# gravicapa.net
KiCad netlist of a schematic drawn in EAGLE
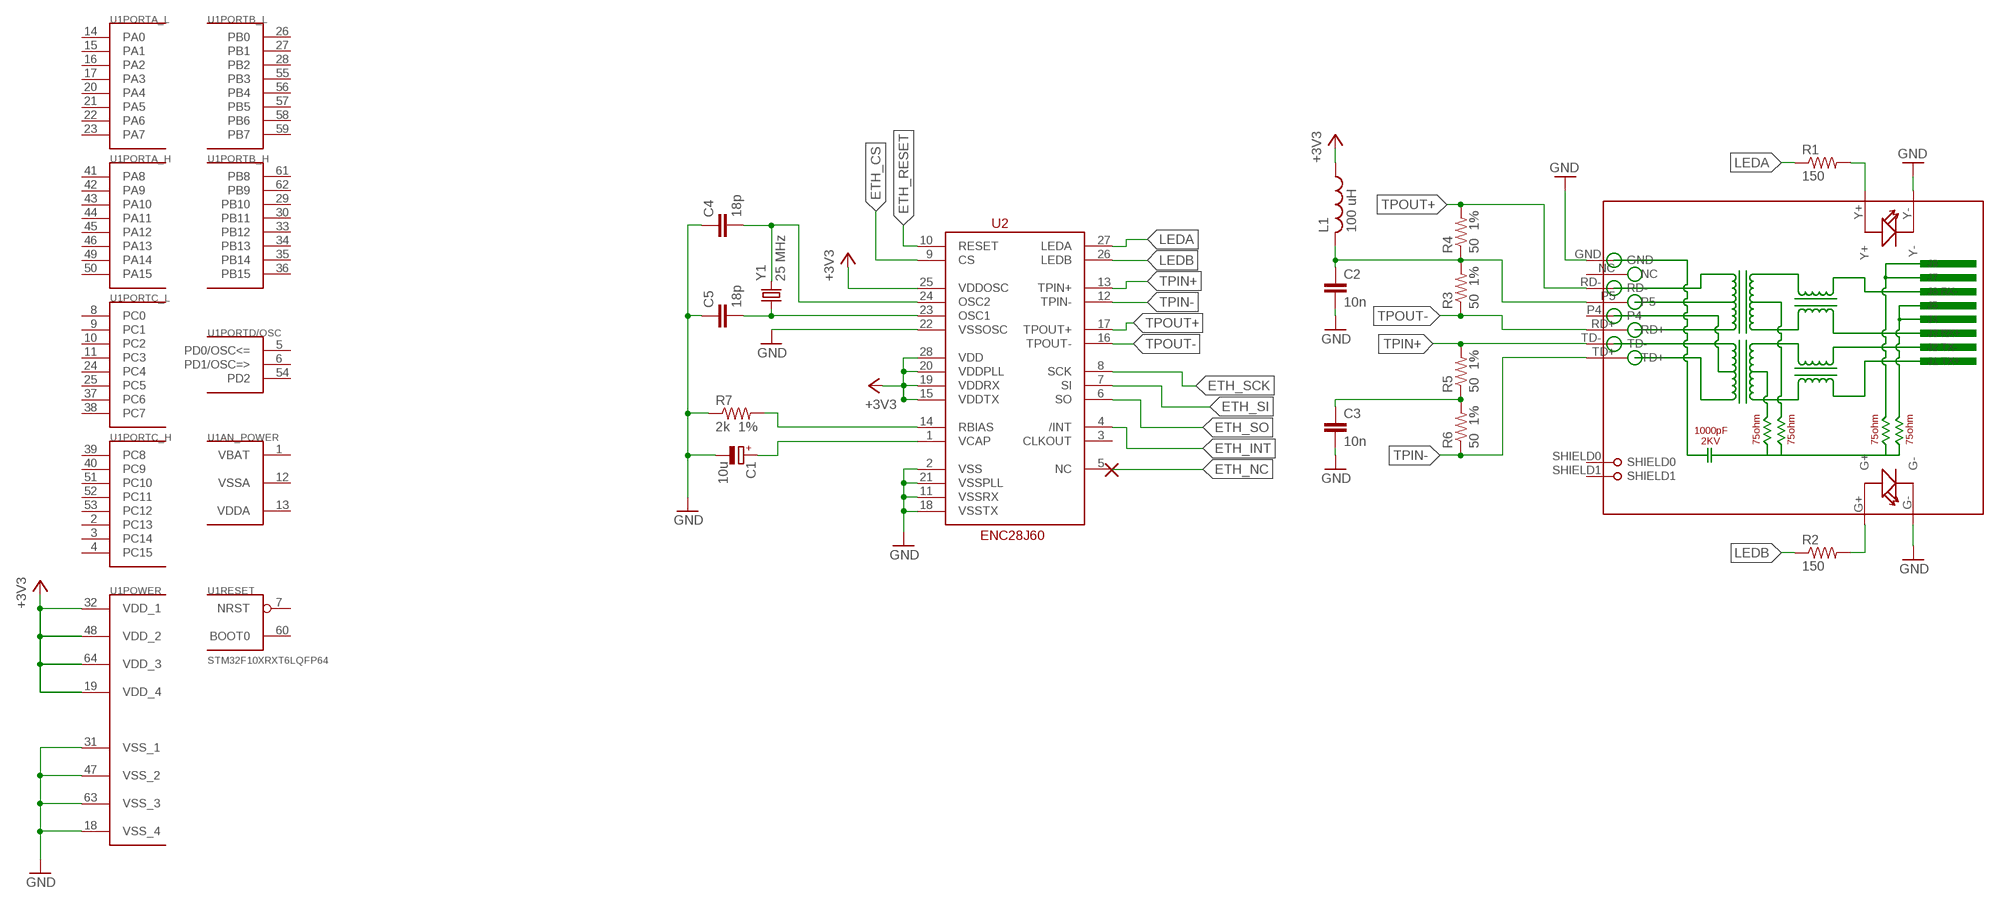
[diagram p0: schematic, sheet 1]

(export (version "E")
  (design (tool "Eeschema 10.0.6"))
  (components
    (comp (ref "C1")
      (value "10u")
      (footprint "eagle-import:SMC_B")
      (libsource (lib "eagle-import") (part "CPOL-EUSMCB"))
    )
    (comp (ref "C2")
      (value "10n")
      (footprint "eagle-import:0805")
      (libsource (lib "eagle-import") (part "CAP0805"))
    )
    (comp (ref "C3")
      (value "10n")
      (footprint "eagle-import:0805")
      (libsource (lib "eagle-import") (part "CAP0805"))
    )
    (comp (ref "C4")
      (value "18p")
      (footprint "eagle-import:0805")
      (libsource (lib "eagle-import") (part "CAP0805"))
    )
    (comp (ref "C5")
      (value "18p")
      (footprint "eagle-import:0805")
      (libsource (lib "eagle-import") (part "CAP0805"))
    )
    (comp (ref "L1")
      (value "100 uH")
      (footprint "eagle-import:POWER-CHOKE_WE-TPC")
      (libsource (lib "eagle-import") (part "L-USWE-TPC"))
    )
    (comp (ref "R1")
      (value "150")
      (footprint "eagle-import:0805")
      (libsource (lib "eagle-import") (part "RESISTOR0805-RES"))
    )
    (comp (ref "R2")
      (value "150")
      (footprint "eagle-import:0805")
      (libsource (lib "eagle-import") (part "RESISTOR0805-RES"))
    )
    (comp (ref "R3")
      (value "50 1%")
      (footprint "eagle-import:0805")
      (libsource (lib "eagle-import") (part "RESISTOR0805-RES"))
    )
    (comp (ref "R4")
      (value "50 1%")
      (footprint "eagle-import:0805")
      (libsource (lib "eagle-import") (part "RESISTOR0805-RES"))
    )
    (comp (ref "R5")
      (value "50 1%")
      (footprint "eagle-import:0805")
      (libsource (lib "eagle-import") (part "RESISTOR0805-RES"))
    )
    (comp (ref "R6")
      (value "50 1%")
      (footprint "eagle-import:0805")
      (libsource (lib "eagle-import") (part "RESISTOR0805-RES"))
    )
    (comp (ref "R7")
      (value "2k 1%")
      (footprint "eagle-import:0805")
      (libsource (lib "eagle-import") (part "RESISTOR0805-RES"))
    )
    (comp (ref "RJ1")
      (value "HR911105A")
      (footprint "eagle-import:HR911105A")
      (libsource (lib "eagle-import") (part "HR911105A"))
    )
    (comp (ref "U1")
      (value "STM32F10XRXT6LQFP64")
      (footprint "eagle-import:LQFP64_MILL")
      (libsource (lib "eagle-import") (part "STM32F10XRXT6LQFP64"))
    )
    (comp (ref "U2")
      (value "ENC28J60")
      (footprint "eagle-import:SSOP28DB")
      (libsource (lib "eagle-import") (part "ENC28J60"))
    )
    (comp (ref "Y1")
      (value "25 MHz")
      (footprint "eagle-import:HC49U-V")
      (libsource (lib "eagle-import") (part "CRYSTALHC49UV"))
    )
  )
  (nets
    (net (code "1") (name "+3V3") (class "Default")
      (node (ref "L1") (pin "1") (pinfunction "1_1") (pintype "passive"))
      (node (ref "U1") (pin "19") (pinfunction "VDD_4_19") (pintype "power_in"))
      (node (ref "U1") (pin "32") (pinfunction "VDD_1_32") (pintype "power_in"))
      (node (ref "U1") (pin "48") (pinfunction "VDD_2_48") (pintype "power_in"))
      (node (ref "U1") (pin "64") (pinfunction "VDD_3_64") (pintype "power_in"))
      (node (ref "U2") (pin "15") (pinfunction "VDDTX_15") (pintype "bidirectional"))
      (node (ref "U2") (pin "19") (pinfunction "VDDRX_19") (pintype "bidirectional"))
      (node (ref "U2") (pin "20") (pinfunction "VDDPLL_20") (pintype "bidirectional"))
      (node (ref "U2") (pin "25") (pinfunction "VDDOSC_25") (pintype "bidirectional"))
      (node (ref "U2") (pin "28") (pinfunction "VDD_28") (pintype "bidirectional"))
    )
    (net (code "2") (name "/VBAT") (class "Default")
      (node (ref "U1") (pin "1") (pinfunction "VBAT_1") (pintype "power_in"))
    )
    (net (code "3") (name "/VDDA") (class "Default")
      (node (ref "U1") (pin "13") (pinfunction "VDDA_13") (pintype "power_in"))
    )
    (net (code "4") (name "/VSSA") (class "Default")
      (node (ref "U1") (pin "12") (pinfunction "VSSA_12") (pintype "power_in"))
    )
    (net (code "5") (name "ETH_CS") (class "Default")
      (node (ref "U2") (pin "9") (pinfunction "CS_9") (pintype "bidirectional"))
    )
    (net (code "6") (name "ETH_INT") (class "Default")
      (node (ref "U2") (pin "4") (pinfunction "/INT_4") (pintype "bidirectional"))
    )
    (net (code "7") (name "ETH_NC") (class "Default")
      (node (ref "U2") (pin "5") (pinfunction "NC_5") (pintype "bidirectional"))
    )
    (net (code "8") (name "ETH_RESET") (class "Default")
      (node (ref "U2") (pin "10") (pinfunction "RESET_10") (pintype "bidirectional"))
    )
    (net (code "9") (name "ETH_SCK") (class "Default")
      (node (ref "U2") (pin "8") (pinfunction "SCK_8") (pintype "bidirectional"))
    )
    (net (code "10") (name "ETH_SI") (class "Default")
      (node (ref "U2") (pin "7") (pinfunction "SI_7") (pintype "bidirectional"))
    )
    (net (code "11") (name "ETH_SO") (class "Default")
      (node (ref "U2") (pin "6") (pinfunction "SO_6") (pintype "bidirectional"))
    )
    (net (code "12") (name "GND") (class "Default")
      (node (ref "C1") (pin "-") (pinfunction "-_-") (pintype "passive"))
      (node (ref "C2") (pin "2") (pinfunction "2_2") (pintype "passive"))
      (node (ref "C3") (pin "2") (pinfunction "2_2") (pintype "passive"))
      (node (ref "C4") (pin "1") (pinfunction "1_1") (pintype "passive"))
      (node (ref "C5") (pin "1") (pinfunction "1_1") (pintype "passive"))
      (node (ref "R7") (pin "1") (pinfunction "1_1") (pintype "passive"))
      (node (ref "RJ1") (pin "G-") (pinfunction "G-_G-") (pintype "bidirectional"))
      (node (ref "RJ1") (pin "GND") (pinfunction "GND_GND") (pintype "bidirectional"))
      (node (ref "RJ1") (pin "Y-") (pinfunction "Y-_Y-") (pintype "bidirectional"))
      (node (ref "U1") (pin "18") (pinfunction "VSS_4_18") (pintype "power_in"))
      (node (ref "U1") (pin "31") (pinfunction "VSS_1_31") (pintype "power_in"))
      (node (ref "U1") (pin "47") (pinfunction "VSS_2_47") (pintype "power_in"))
      (node (ref "U1") (pin "63") (pinfunction "VSS_3_63") (pintype "power_in"))
      (node (ref "U2") (pin "11") (pinfunction "VSSRX_11") (pintype "bidirectional"))
      (node (ref "U2") (pin "18") (pinfunction "VSSTX_18") (pintype "bidirectional"))
      (node (ref "U2") (pin "2") (pinfunction "VSS_2") (pintype "bidirectional"))
      (node (ref "U2") (pin "21") (pinfunction "VSSPLL_21") (pintype "bidirectional"))
      (node (ref "U2") (pin "22") (pinfunction "VSSOSC_22") (pintype "bidirectional"))
    )
    (net (code "13") (name "LEDA") (class "Default")
      (node (ref "R1") (pin "1") (pinfunction "1_1") (pintype "passive"))
      (node (ref "U2") (pin "27") (pinfunction "LEDA_27") (pintype "bidirectional"))
    )
    (net (code "14") (name "LEDB") (class "Default")
      (node (ref "R2") (pin "1") (pinfunction "1_1") (pintype "passive"))
      (node (ref "U2") (pin "26") (pinfunction "LEDB_26") (pintype "bidirectional"))
    )
    (net (code "15") (name "Net-(C2-Pad1)") (class "Default")
      (node (ref "C2") (pin "1") (pinfunction "1_1") (pintype "passive"))
      (node (ref "L1") (pin "2") (pinfunction "2_2") (pintype "passive"))
      (node (ref "R3") (pin "2") (pinfunction "2_2") (pintype "passive"))
      (node (ref "R4") (pin "1") (pinfunction "1_1") (pintype "passive"))
      (node (ref "RJ1") (pin "P5") (pinfunction "P5_P5") (pintype "bidirectional"))
    )
    (net (code "16") (name "Net-(C3-Pad1)") (class "Default")
      (node (ref "C3") (pin "1") (pinfunction "1_1") (pintype "passive"))
      (node (ref "R5") (pin "1") (pinfunction "1_1") (pintype "passive"))
      (node (ref "R6") (pin "2") (pinfunction "2_2") (pintype "passive"))
    )
    (net (code "17") (name "Net-(R1-Pad2)") (class "Default")
      (node (ref "R1") (pin "2") (pinfunction "2_2") (pintype "passive"))
      (node (ref "RJ1") (pin "Y+") (pinfunction "Y+_Y+") (pintype "bidirectional"))
    )
    (net (code "18") (name "Net-(R2-Pad2)") (class "Default")
      (node (ref "R2") (pin "2") (pinfunction "2_2") (pintype "passive"))
      (node (ref "RJ1") (pin "G+") (pinfunction "G+_G+") (pintype "bidirectional"))
    )
    (net (code "19") (name "Net-(U2-OSC1)") (class "Default")
      (node (ref "C5") (pin "2") (pinfunction "2_2") (pintype "passive"))
      (node (ref "U2") (pin "23") (pinfunction "OSC1_23") (pintype "bidirectional"))
      (node (ref "Y1") (pin "1") (pinfunction "1_1") (pintype "passive"))
    )
    (net (code "20") (name "Net-(U2-OSC2)") (class "Default")
      (node (ref "C4") (pin "2") (pinfunction "2_2") (pintype "passive"))
      (node (ref "U2") (pin "24") (pinfunction "OSC2_24") (pintype "bidirectional"))
      (node (ref "Y1") (pin "2") (pinfunction "2_2") (pintype "passive"))
    )
    (net (code "21") (name "Net-(U2-RBIAS)") (class "Default")
      (node (ref "R7") (pin "2") (pinfunction "2_2") (pintype "passive"))
      (node (ref "U2") (pin "14") (pinfunction "RBIAS_14") (pintype "bidirectional"))
    )
    (net (code "22") (name "Net-(U2-VCAP)") (class "Default")
      (node (ref "C1") (pin "+") (pinfunction "+_+") (pintype "passive"))
      (node (ref "U2") (pin "1") (pinfunction "VCAP_1") (pintype "bidirectional"))
    )
    (net (code "23") (name "TPIN+") (class "Default")
      (node (ref "R5") (pin "2") (pinfunction "2_2") (pintype "passive"))
      (node (ref "RJ1") (pin "TD-") (pinfunction "TD-_TD-") (pintype "bidirectional"))
      (node (ref "U2") (pin "13") (pinfunction "TPIN+_13") (pintype "bidirectional"))
    )
    (net (code "24") (name "TPIN-") (class "Default")
      (node (ref "R6") (pin "1") (pinfunction "1_1") (pintype "passive"))
      (node (ref "RJ1") (pin "TD+") (pinfunction "TD+_TD+") (pintype "bidirectional"))
      (node (ref "U2") (pin "12") (pinfunction "TPIN-_12") (pintype "bidirectional"))
    )
    (net (code "25") (name "TPOUT+") (class "Default")
      (node (ref "R4") (pin "2") (pinfunction "2_2") (pintype "passive"))
      (node (ref "RJ1") (pin "RD-") (pinfunction "RD-_RD-") (pintype "bidirectional"))
      (node (ref "U2") (pin "17") (pinfunction "TPOUT+_17") (pintype "bidirectional"))
    )
    (net (code "26") (name "TPOUT-") (class "Default")
      (node (ref "R3") (pin "1") (pinfunction "1_1") (pintype "passive"))
      (node (ref "RJ1") (pin "RD+") (pinfunction "RD+_RD+") (pintype "bidirectional"))
      (node (ref "U2") (pin "16") (pinfunction "TPOUT-_16") (pintype "bidirectional"))
    )
    (net (code "27") (name "unconnected-(RJ1-PadNC)") (class "Default")
      (node (ref "RJ1") (pin "NC") (pinfunction "NC_NC") (pintype "bidirectional"))
    )
    (net (code "28") (name "unconnected-(RJ1-PadP4)") (class "Default")
      (node (ref "RJ1") (pin "P4") (pinfunction "P4_P4") (pintype "bidirectional"))
    )
    (net (code "29") (name "unconnected-(RJ1-PadSHIELD0)") (class "Default")
      (node (ref "RJ1") (pin "SHIELD0") (pinfunction "SHIELD0_SHIELD0") (pintype "bidirectional"))
    )
    (net (code "30") (name "unconnected-(RJ1-PadSHIELD1)") (class "Default")
      (node (ref "RJ1") (pin "SHIELD1") (pinfunction "SHIELD1_SHIELD1") (pintype "bidirectional"))
    )
    (net (code "31") (name "unconnected-(U1B-PA8-Pad41)") (class "Default")
      (node (ref "U1") (pin "41") (pinfunction "PA8_41") (pintype "bidirectional"))
    )
    (net (code "32") (name "unconnected-(U1B-PA9-Pad42)") (class "Default")
      (node (ref "U1") (pin "42") (pinfunction "PA9_42") (pintype "bidirectional"))
    )
    (net (code "33") (name "unconnected-(U1B-PA10-Pad43)") (class "Default")
      (node (ref "U1") (pin "43") (pinfunction "PA10_43") (pintype "bidirectional"))
    )
    (net (code "34") (name "unconnected-(U1B-PA11-Pad44)") (class "Default")
      (node (ref "U1") (pin "44") (pinfunction "PA11_44") (pintype "bidirectional"))
    )
    (net (code "35") (name "unconnected-(U1B-PA12-Pad45)") (class "Default")
      (node (ref "U1") (pin "45") (pinfunction "PA12_45") (pintype "bidirectional"))
    )
    (net (code "36") (name "unconnected-(U1B-PA13-Pad46)") (class "Default")
      (node (ref "U1") (pin "46") (pinfunction "PA13_46") (pintype "bidirectional"))
    )
    (net (code "37") (name "unconnected-(U1B-PA14-Pad49)") (class "Default")
      (node (ref "U1") (pin "49") (pinfunction "PA14_49") (pintype "bidirectional"))
    )
    (net (code "38") (name "unconnected-(U1B-PA15-Pad50)") (class "Default")
      (node (ref "U1") (pin "50") (pinfunction "PA15_50") (pintype "bidirectional"))
    )
    (net (code "39") (name "unconnected-(U1C-PA0-Pad14)") (class "Default")
      (node (ref "U1") (pin "14") (pinfunction "PA0_14") (pintype "bidirectional"))
    )
    (net (code "40") (name "unconnected-(U1C-PA1-Pad15)") (class "Default")
      (node (ref "U1") (pin "15") (pinfunction "PA1_15") (pintype "bidirectional"))
    )
    (net (code "41") (name "unconnected-(U1C-PA2-Pad16)") (class "Default")
      (node (ref "U1") (pin "16") (pinfunction "PA2_16") (pintype "bidirectional"))
    )
    (net (code "42") (name "unconnected-(U1C-PA3-Pad17)") (class "Default")
      (node (ref "U1") (pin "17") (pinfunction "PA3_17") (pintype "bidirectional"))
    )
    (net (code "43") (name "unconnected-(U1C-PA4-Pad20)") (class "Default")
      (node (ref "U1") (pin "20") (pinfunction "PA4_20") (pintype "bidirectional"))
    )
    (net (code "44") (name "unconnected-(U1C-PA5-Pad21)") (class "Default")
      (node (ref "U1") (pin "21") (pinfunction "PA5_21") (pintype "bidirectional"))
    )
    (net (code "45") (name "unconnected-(U1C-PA6-Pad22)") (class "Default")
      (node (ref "U1") (pin "22") (pinfunction "PA6_22") (pintype "bidirectional"))
    )
    (net (code "46") (name "unconnected-(U1C-PA7-Pad23)") (class "Default")
      (node (ref "U1") (pin "23") (pinfunction "PA7_23") (pintype "bidirectional"))
    )
    (net (code "47") (name "unconnected-(U1D-PB8-Pad61)") (class "Default")
      (node (ref "U1") (pin "61") (pinfunction "PB8_61") (pintype "bidirectional"))
    )
    (net (code "48") (name "unconnected-(U1D-PB9-Pad62)") (class "Default")
      (node (ref "U1") (pin "62") (pinfunction "PB9_62") (pintype "bidirectional"))
    )
    (net (code "49") (name "unconnected-(U1D-PB10-Pad29)") (class "Default")
      (node (ref "U1") (pin "29") (pinfunction "PB10_29") (pintype "bidirectional"))
    )
    (net (code "50") (name "unconnected-(U1D-PB11-Pad30)") (class "Default")
      (node (ref "U1") (pin "30") (pinfunction "PB11_30") (pintype "bidirectional"))
    )
    (net (code "51") (name "unconnected-(U1D-PB12-Pad33)") (class "Default")
      (node (ref "U1") (pin "33") (pinfunction "PB12_33") (pintype "bidirectional"))
    )
    (net (code "52") (name "unconnected-(U1D-PB13-Pad34)") (class "Default")
      (node (ref "U1") (pin "34") (pinfunction "PB13_34") (pintype "bidirectional"))
    )
    (net (code "53") (name "unconnected-(U1D-PB14-Pad35)") (class "Default")
      (node (ref "U1") (pin "35") (pinfunction "PB14_35") (pintype "bidirectional"))
    )
    (net (code "54") (name "unconnected-(U1D-PB15-Pad36)") (class "Default")
      (node (ref "U1") (pin "36") (pinfunction "PB15_36") (pintype "bidirectional"))
    )
    (net (code "55") (name "unconnected-(U1E-PB0-Pad26)") (class "Default")
      (node (ref "U1") (pin "26") (pinfunction "PB0_26") (pintype "bidirectional"))
    )
    (net (code "56") (name "unconnected-(U1E-PB1-Pad27)") (class "Default")
      (node (ref "U1") (pin "27") (pinfunction "PB1_27") (pintype "bidirectional"))
    )
    (net (code "57") (name "unconnected-(U1E-PB2-Pad28)") (class "Default")
      (node (ref "U1") (pin "28") (pinfunction "PB2_28") (pintype "bidirectional"))
    )
    (net (code "58") (name "unconnected-(U1E-PB3-Pad55)") (class "Default")
      (node (ref "U1") (pin "55") (pinfunction "PB3_55") (pintype "bidirectional"))
    )
    (net (code "59") (name "unconnected-(U1E-PB4-Pad56)") (class "Default")
      (node (ref "U1") (pin "56") (pinfunction "PB4_56") (pintype "bidirectional"))
    )
    (net (code "60") (name "unconnected-(U1E-PB5-Pad57)") (class "Default")
      (node (ref "U1") (pin "57") (pinfunction "PB5_57") (pintype "bidirectional"))
    )
    (net (code "61") (name "unconnected-(U1E-PB6-Pad58)") (class "Default")
      (node (ref "U1") (pin "58") (pinfunction "PB6_58") (pintype "bidirectional"))
    )
    (net (code "62") (name "unconnected-(U1E-PB7-Pad59)") (class "Default")
      (node (ref "U1") (pin "59") (pinfunction "PB7_59") (pintype "bidirectional"))
    )
    (net (code "63") (name "unconnected-(U1F-PC8-Pad39)") (class "Default")
      (node (ref "U1") (pin "39") (pinfunction "PC8_39") (pintype "bidirectional"))
    )
    (net (code "64") (name "unconnected-(U1F-PC9-Pad40)") (class "Default")
      (node (ref "U1") (pin "40") (pinfunction "PC9_40") (pintype "bidirectional"))
    )
    (net (code "65") (name "unconnected-(U1F-PC10-Pad51)") (class "Default")
      (node (ref "U1") (pin "51") (pinfunction "PC10_51") (pintype "bidirectional"))
    )
    (net (code "66") (name "unconnected-(U1F-PC11-Pad52)") (class "Default")
      (node (ref "U1") (pin "52") (pinfunction "PC11_52") (pintype "bidirectional"))
    )
    (net (code "67") (name "unconnected-(U1F-PC12-Pad53)") (class "Default")
      (node (ref "U1") (pin "53") (pinfunction "PC12_53") (pintype "bidirectional"))
    )
    (net (code "68") (name "unconnected-(U1F-PC13-Pad2)") (class "Default")
      (node (ref "U1") (pin "2") (pinfunction "PC13_2") (pintype "bidirectional"))
    )
    (net (code "69") (name "unconnected-(U1F-PC14-Pad3)") (class "Default")
      (node (ref "U1") (pin "3") (pinfunction "PC14_3") (pintype "bidirectional"))
    )
    (net (code "70") (name "unconnected-(U1F-PC15-Pad4)") (class "Default")
      (node (ref "U1") (pin "4") (pinfunction "PC15_4") (pintype "bidirectional"))
    )
    (net (code "71") (name "unconnected-(U1G-PC0-Pad8)") (class "Default")
      (node (ref "U1") (pin "8") (pinfunction "PC0_8") (pintype "bidirectional"))
    )
    (net (code "72") (name "unconnected-(U1G-PC1-Pad9)") (class "Default")
      (node (ref "U1") (pin "9") (pinfunction "PC1_9") (pintype "bidirectional"))
    )
    (net (code "73") (name "unconnected-(U1G-PC2-Pad10)") (class "Default")
      (node (ref "U1") (pin "10") (pinfunction "PC2_10") (pintype "bidirectional"))
    )
    (net (code "74") (name "unconnected-(U1G-PC3-Pad11)") (class "Default")
      (node (ref "U1") (pin "11") (pinfunction "PC3_11") (pintype "bidirectional"))
    )
    (net (code "75") (name "unconnected-(U1G-PC4-Pad24)") (class "Default")
      (node (ref "U1") (pin "24") (pinfunction "PC4_24") (pintype "bidirectional"))
    )
    (net (code "76") (name "unconnected-(U1G-PC5-Pad25)") (class "Default")
      (node (ref "U1") (pin "25") (pinfunction "PC5_25") (pintype "bidirectional"))
    )
    (net (code "77") (name "unconnected-(U1G-PC6-Pad37)") (class "Default")
      (node (ref "U1") (pin "37") (pinfunction "PC6_37") (pintype "bidirectional"))
    )
    (net (code "78") (name "unconnected-(U1G-PC7-Pad38)") (class "Default")
      (node (ref "U1") (pin "38") (pinfunction "PC7_38") (pintype "bidirectional"))
    )
    (net (code "79") (name "unconnected-(U1H-PD0{slash}OSC<=-Pad5)") (class "Default")
      (node (ref "U1") (pin "5") (pinfunction "PD0/OSC<=_5") (pintype "bidirectional"))
    )
    (net (code "80") (name "unconnected-(U1H-PD1{slash}OSC=>-Pad6)") (class "Default")
      (node (ref "U1") (pin "6") (pinfunction "PD1/OSC=>_6") (pintype "bidirectional"))
    )
    (net (code "81") (name "unconnected-(U1H-PD2-Pad54)") (class "Default")
      (node (ref "U1") (pin "54") (pinfunction "PD2_54") (pintype "bidirectional"))
    )
    (net (code "82") (name "unconnected-(U1J-BOOT0-Pad60)") (class "Default")
      (node (ref "U1") (pin "60") (pinfunction "BOOT0_60") (pintype "input"))
    )
    (net (code "83") (name "unconnected-(U1J-NRST-Pad7)") (class "Default")
      (node (ref "U1") (pin "7") (pinfunction "NRST_7") (pintype "input"))
    )
    (net (code "84") (name "unconnected-(U2-CLKOUT-Pad3)") (class "Default")
      (node (ref "U2") (pin "3") (pinfunction "CLKOUT_3") (pintype "bidirectional"))
    )
  )
)
